# Peripheral.net
KiCad netlist of a schematic drawn in Altium Designer
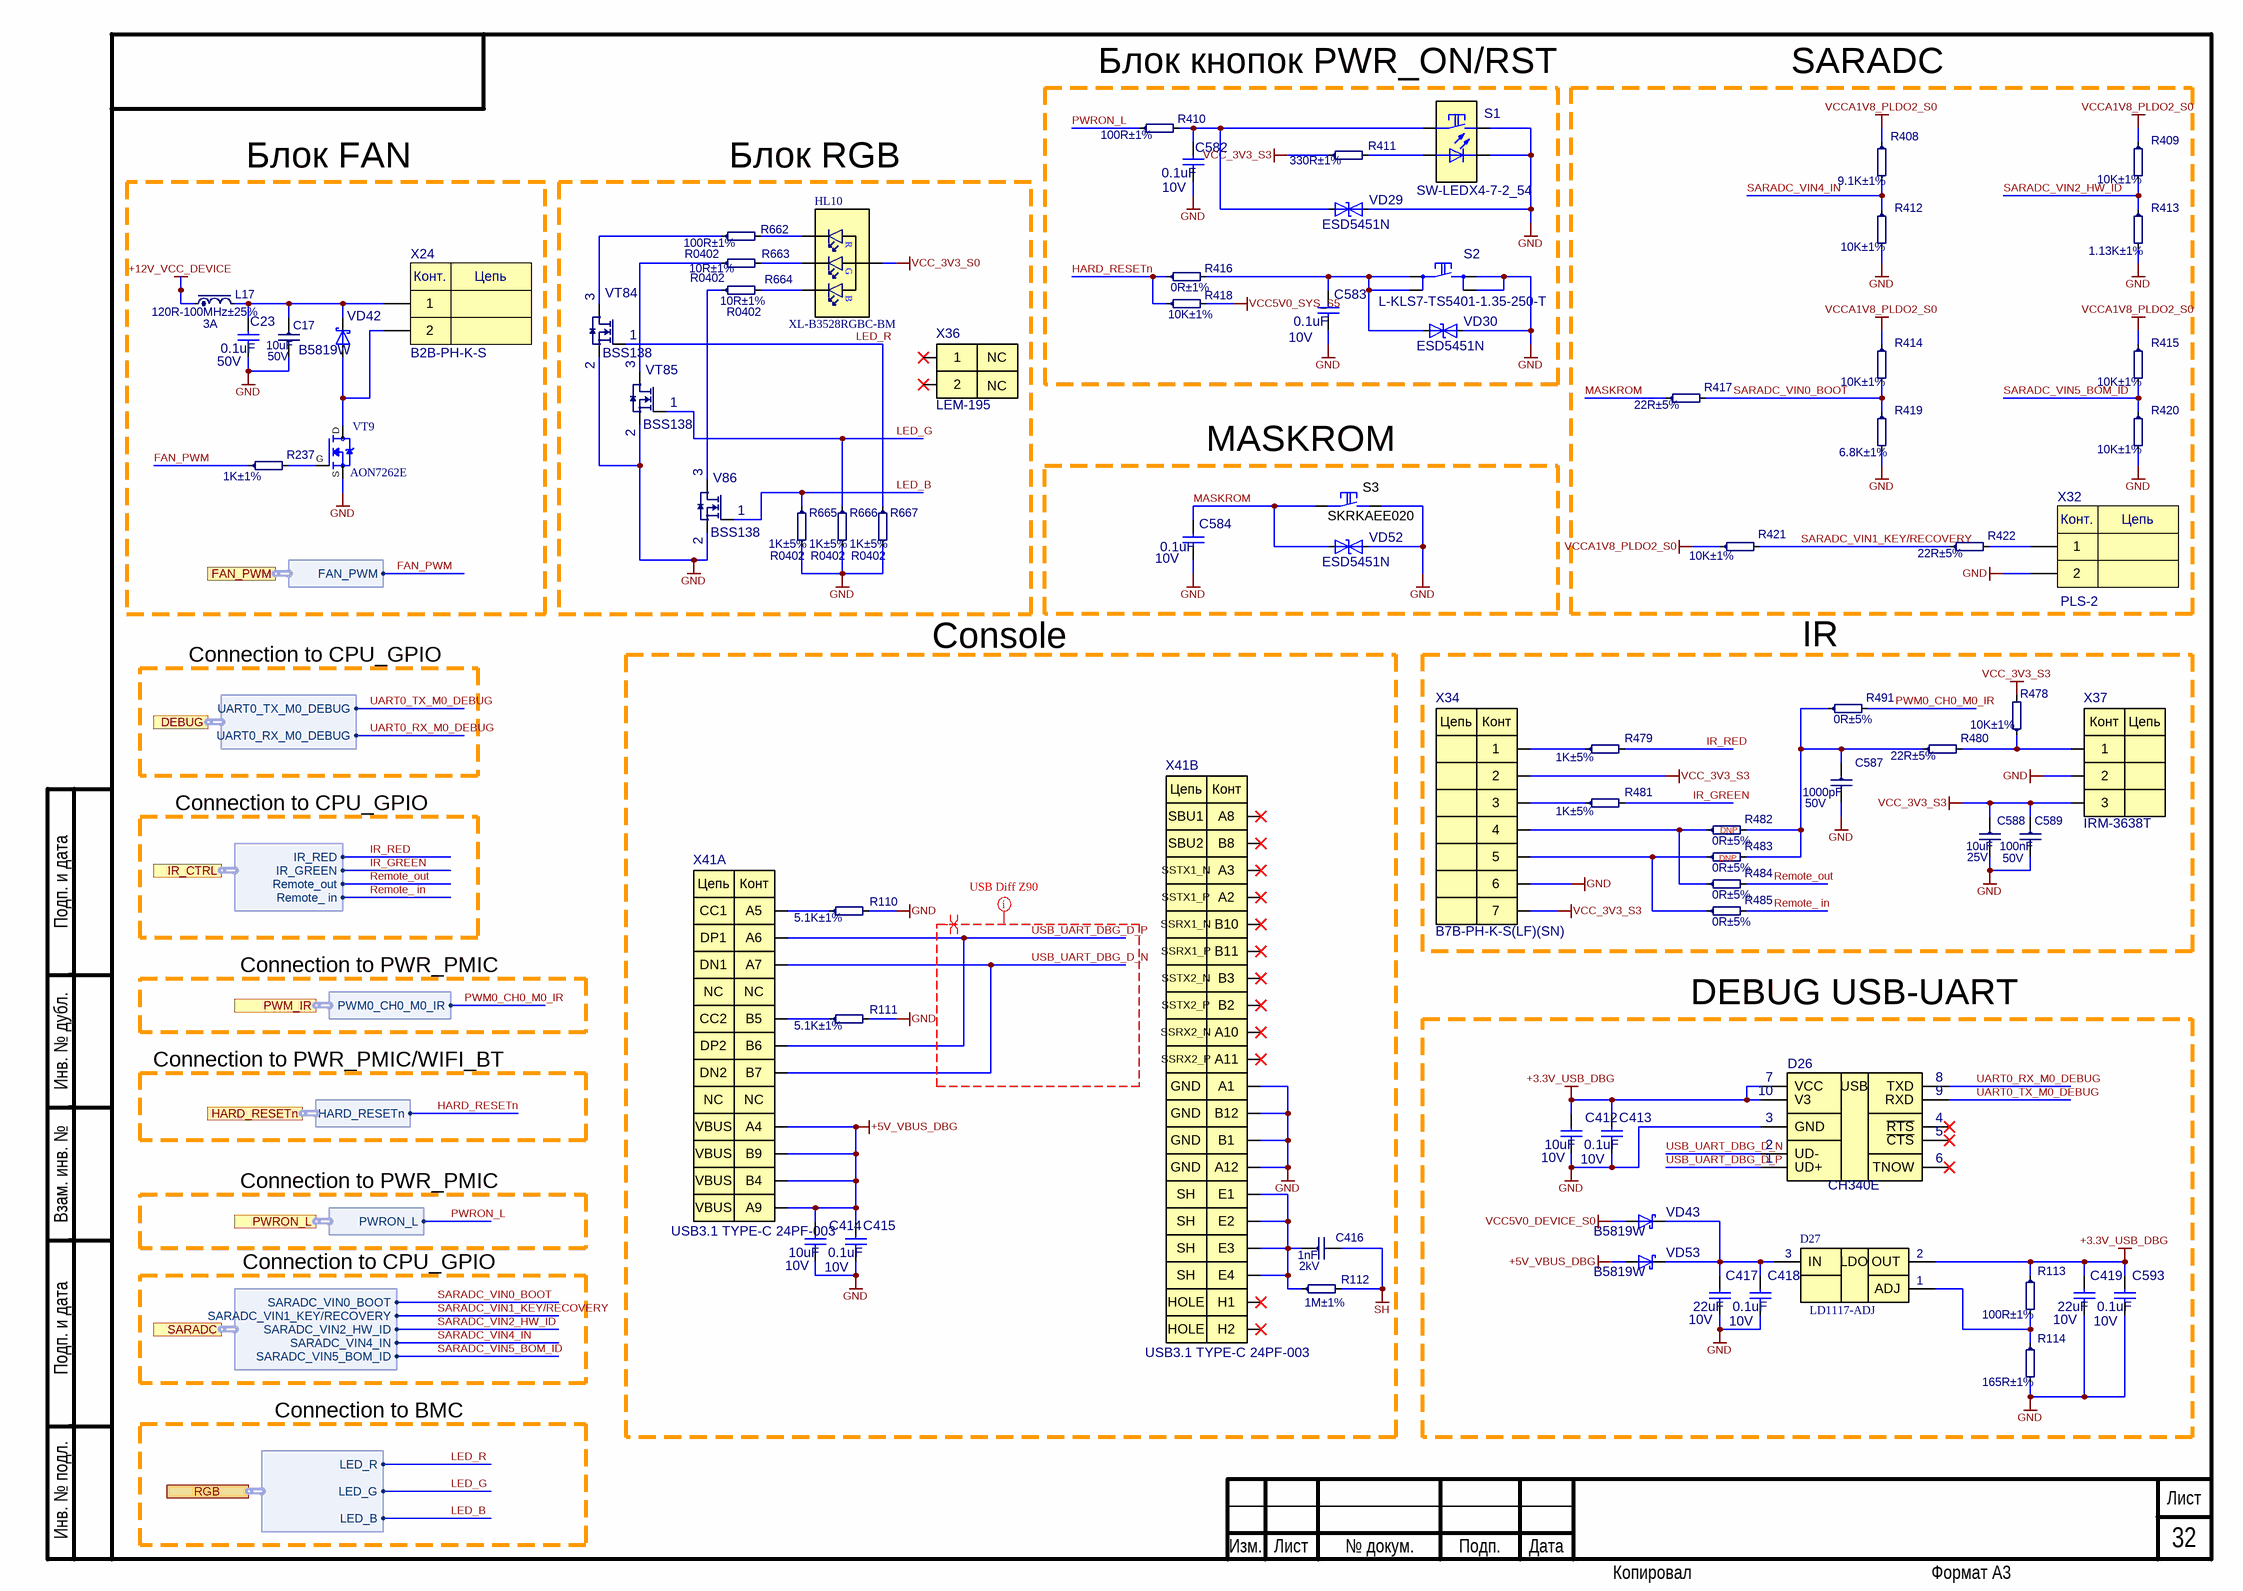
[diagram p0: Peripheral.SchDoc]

(export (version "E")
  (design (tool "Eeschema 10.0.6"))
  (components
    (comp (ref "C17")
      (value "10uF")
      (footprint "C1206")
      (fields
        (field (name "VOLTAGE") "50V")
        (field (name "PART NUMBER") "1206-X5R-50V-010uF±10%")
        (field (name "TOLERANCE") "10%")
        (field (name "MANUFACTURER") "Yageo")
      )
      (libsource (lib "") (part "C_1"))
    )
    (comp (ref "C23")
      (value "0.1uF")
      (footprint "C0402")
      (fields
        (field (name "PART NUMBER") "0402-X5R-50V-0.1uF±10%")
        (field (name "VOLTAGE") "50V")
        (field (name "TOLERANCE") "10%")
        (field (name "MANUFACTURER") "Yageo")
      )
      (libsource (lib "ATB") (part "C"))
    )
    (comp (ref "C412")
      (value "10uF")
      (footprint "C0402")
      (fields
        (field (name "PART NUMBER") "0402-X5R-10V-10uF±20%")
        (field (name "VOLTAGE") "10V")
        (field (name "TOLERANCE") "20%")
        (field (name "MANUFACTURER") "Murata Electronics")
      )
      (libsource (lib "ATB") (part "C"))
    )
    (comp (ref "C413")
      (value "0.1uF")
      (footprint "C0402")
      (fields
        (field (name "PART NUMBER") "0402-X5R-10V-0.1uF±10%")
        (field (name "VOLTAGE") "10V")
        (field (name "TOLERANCE") "10%")
        (field (name "MANUFACTURER") "Yageo")
      )
      (libsource (lib "ATB") (part "C"))
    )
    (comp (ref "C414")
      (value "10uF")
      (footprint "C0402")
      (fields
        (field (name "PART NUMBER") "0402-X5R-10V-10uF±20%")
        (field (name "VOLTAGE") "10V")
        (field (name "TOLERANCE") "20%")
        (field (name "MANUFACTURER") "Murata Electronics")
      )
      (libsource (lib "ATB") (part "C"))
    )
    (comp (ref "C415")
      (value "0.1uF")
      (footprint "C0402")
      (fields
        (field (name "PART NUMBER") "0402-X5R-10V-0.1uF±10%")
        (field (name "VOLTAGE") "10V")
        (field (name "TOLERANCE") "10%")
        (field (name "MANUFACTURER") "Yageo")
      )
      (libsource (lib "ATB") (part "C"))
    )
    (comp (ref "C416")
      (value "1nF")
      (footprint "C1812")
      (fields
        (field (name "VOLTAGE") "2kV")
        (field (name "PART NUMBER") "1812-C0G-2kV-1nF±10%")
        (field (name "TOLERANCE") "5%")
        (field (name "MANUFACTURER") "FH")
      )
      (libsource (lib "") (part "C_1"))
    )
    (comp (ref "C417")
      (value "22uF")
      (footprint "C0603")
      (fields
        (field (name "PART NUMBER") "0603-X5R-10V-22uF±20%")
        (field (name "VOLTAGE") "10V")
        (field (name "TOLERANCE") "20%")
        (field (name "MANUFACTURER") "Murata")
      )
      (libsource (lib "ATB") (part "C"))
    )
    (comp (ref "C418")
      (value "0.1uF")
      (footprint "C0402")
      (fields
        (field (name "PART NUMBER") "0402-X5R-10V-0.1uF±10%")
        (field (name "VOLTAGE") "10V")
        (field (name "TOLERANCE") "10%")
        (field (name "MANUFACTURER") "Yageo")
      )
      (libsource (lib "ATB") (part "C"))
    )
    (comp (ref "C419")
      (value "22uF")
      (footprint "C0603")
      (fields
        (field (name "PART NUMBER") "0603-X5R-10V-22uF±20%")
        (field (name "VOLTAGE") "10V")
        (field (name "TOLERANCE") "20%")
        (field (name "MANUFACTURER") "Murata")
      )
      (libsource (lib "ATB") (part "C"))
    )
    (comp (ref "C582")
      (value "0.1uF")
      (footprint "C0402")
      (fields
        (field (name "PART NUMBER") "0402-X5R-10V-0.1uF±10%")
        (field (name "VOLTAGE") "10V")
        (field (name "TOLERANCE") "10%")
        (field (name "MANUFACTURER") "Yageo")
      )
      (libsource (lib "ATB") (part "C"))
    )
    (comp (ref "C583")
      (value "0.1uF")
      (footprint "C0402")
      (fields
        (field (name "PART NUMBER") "0402-X5R-10V-0.1uF±10%")
        (field (name "VOLTAGE") "10V")
        (field (name "TOLERANCE") "10%")
        (field (name "MANUFACTURER") "Yageo")
      )
      (libsource (lib "ATB") (part "C"))
    )
    (comp (ref "C584")
      (value "0.1uF")
      (footprint "C0402")
      (fields
        (field (name "PART NUMBER") "0402-X5R-10V-0.1uF±10%")
        (field (name "VOLTAGE") "10V")
        (field (name "TOLERANCE") "10%")
        (field (name "MANUFACTURER") "Yageo")
      )
      (libsource (lib "ATB") (part "C"))
    )
    (comp (ref "C587")
      (value "1000pF")
      (footprint "C0402")
      (fields
        (field (name "VOLTAGE") "50V")
        (field (name "PART NUMBER") "0402-NP0-50V-1000pF±5%")
        (field (name "TOLERANCE") "5%")
        (field (name "MANUFACTURER") "Yageo")
      )
      (libsource (lib "") (part "C_1"))
    )
    (comp (ref "C588")
      (value "10uF")
      (footprint "C0805")
      (fields
        (field (name "VOLTAGE") "25V")
        (field (name "PART NUMBER") "0805-X5R-25V-10uF±10%")
        (field (name "TOLERANCE") "10%")
        (field (name "MANUFACTURER") "Samsung")
      )
      (libsource (lib "") (part "C_1"))
    )
    (comp (ref "C589")
      (value "100nF")
      (footprint "C0402")
      (description "Ceramic Capacitor 0402 100nF ±10% 50V X7R")
      (fields
        (field (name "VOLTAGE") "50V")
        (field (name "PART NUMBER") "0402-X7R-50V-0.1uF±10%")
        (field (name "TOLERANCE") "10%")
      )
      (libsource (lib "") (part "C_1"))
    )
    (comp (ref "C593")
      (value "0.1uF")
      (footprint "C0402")
      (fields
        (field (name "PART NUMBER") "0402-X5R-10V-0.1uF±10%")
        (field (name "VOLTAGE") "10V")
        (field (name "TOLERANCE") "10%")
        (field (name "MANUFACTURER") "Yageo")
      )
      (libsource (lib "ATB") (part "C"))
    )
    (comp (ref "D26")
      (value "CH340E")
      (footprint "MSOP-10")
      (description "USB to serial chip")
      (fields (field (name "MANUFACTURER") "WCH"))
      (libsource (lib "ATB") (part "CH340E"))
    )
    (comp (ref "D27")
      (value "LD1117-ADJ")
      (footprint "GM1117S-AST3R")
      (fields (field (name "MANUFACTURER") "UMW"))
      (libsource (lib "LIB_RK") (part "GM1117S-AST3R"))
    )
    (comp (ref "HL10")
      (value "XL-B3528RGBC-BM")
      (footprint "XL-B3528RGBC-BM")
      (description "20mA 无色透明透镜 -40℃~+85℃ Common anode 正贴 RGB 45mW SMD2835-4P Light Emitting Diodes (LED) ROHS")
      (fields (field (name "MANUFACTURER") "XINGLIGHT"))
      (libsource (lib "LIB_RK") (part "XL-B3528RGBC-BM"))
    )
    (comp (ref "L17")
      (value "120R-100MHz±25%")
      (footprint "L0805")
      (fields
        (field (name "CURRENT") "3A")
        (field (name "PART NUMBER") "0805-3A-120R-100MHz")
        (field (name "TOLERANCE") "25%")
        (field (name "MANUFACTURER") "Murata Electronics")
      )
      (libsource (lib "ATB") (part "L"))
    )
    (comp (ref "R110")
      (value "5.1K±1%")
      (footprint "R0402")
      (description "Chip Resistor 0402 5.1kΩ ±1% 50V ±100ppm/℃ Thick Film")
      (fields (field (name "PART NUMBER") "0402-0.0625W-5.1K-100ppm±1%") (field (name "TOLERANCE") "1%"))
      (libsource (lib "ATB") (part "R"))
    )
    (comp (ref "R111")
      (value "5.1K±1%")
      (footprint "R0402")
      (description "Chip Resistor 0402 5.1kΩ ±1% 50V ±100ppm/℃ Thick Film")
      (fields (field (name "PART NUMBER") "0402-0.0625W-5.1K-100ppm±1%") (field (name "TOLERANCE") "1%"))
      (libsource (lib "ATB") (part "R"))
    )
    (comp (ref "R112")
      (value "1M±1%")
      (footprint "R1206")
      (description "Chip Resistor 1206 1MΩ ±1% 200V ±100ppm/℃ Thick Film")
      (fields (field (name "PART NUMBER") "1206-0.25W-1M-100ppm±1%") (field (name "TOLERANCE") "1%"))
      (libsource (lib "ATB") (part "R"))
    )
    (comp (ref "R113")
      (value "100R±1%")
      (footprint "R0402")
      (description "Chip Resistor 0402 100Ω ±1% 50V ±100ppm/℃ Thick Film")
      (fields (field (name "PART NUMBER") "0402-0.0625W-100R-100ppm±1%") (field (name "TOLERANCE") "1%"))
      (libsource (lib "ATB") (part "R"))
    )
    (comp (ref "R114")
      (value "165R±1%")
      (footprint "R0402")
      (description "Chip Resistor 0402 100Ω ±1% 50V ±100ppm/℃ Thick Film")
      (fields (field (name "PART NUMBER") "0402-0.0625W-165R-100ppm±1%") (field (name "TOLERANCE") "1%"))
      (libsource (lib "ATB") (part "R"))
    )
    (comp (ref "R237")
      (value "1K±1%")
      (footprint "R0402")
      (fields
        (field (name "PART NUMBER") "0402-0.0625W-1K-100ppm±1%")
        (field (name "TOLERANCE") "1%")
        (field (name "MANUFACTURER") "Yageo")
      )
      (libsource (lib "ATB") (part "R"))
    )
    (comp (ref "R408")
      (value "9.1K±1%")
      (footprint "R0402")
      (fields
        (field (name "PART NUMBER") "0402-0.0625W-9.1K-100ppm±1%")
        (field (name "TOLERANCE") "1%")
        (field (name "MANUFACTURER") "Yageo")
      )
      (libsource (lib "ATB") (part "R"))
    )
    (comp (ref "R409")
      (value "10K±1%")
      (footprint "R0402")
      (description "Chip Resistor 0402 10kΩ ±1% 50V ±100ppm/℃ Thick Film")
      (fields (field (name "PART NUMBER") "0402-0.0625W-10K-100ppm±1%") (field (name "TOLERANCE") "1%"))
      (libsource (lib "ATB") (part "R"))
    )
    (comp (ref "R410")
      (value "100R±1%")
      (footprint "R0402")
      (description "Chip Resistor 0402 100Ω ±1% 50V ±100ppm/℃ Thick Film")
      (fields (field (name "PART NUMBER") "0402-0.0625W-100R-100ppm±1%") (field (name "TOLERANCE") "1%"))
      (libsource (lib "ATB") (part "R"))
    )
    (comp (ref "R411")
      (value "330R±1%")
      (footprint "R0402")
      (fields
        (field (name "PART NUMBER") "0402-0.0625W-330R-100ppm±1%")
        (field (name "TOLERANCE") "1%")
        (field (name "MANUFACTURER") "Yageo")
      )
      (libsource (lib "ATB") (part "R"))
    )
    (comp (ref "R412")
      (value "10K±1%")
      (footprint "R0402")
      (description "Chip Resistor 0402 10kΩ ±1% 50V ±100ppm/℃ Thick Film")
      (fields (field (name "PART NUMBER") "0402-0.0625W-10K-100ppm±1%") (field (name "TOLERANCE") "1%"))
      (libsource (lib "ATB") (part "R"))
    )
    (comp (ref "R413")
      (value "1.13K±1%")
      (footprint "R0402")
      (description "Chip Resistor 0402 10kΩ ±1% 50V ±100ppm/℃ Thick Film")
      (fields (field (name "PART NUMBER") "0402-0.0625W-1.13K-100ppm±1%") (field (name "TOLERANCE") "1%"))
      (libsource (lib "ATB") (part "R"))
    )
    (comp (ref "R414")
      (value "10K±1%")
      (footprint "R0402")
      (description "Chip Resistor 0402 10kΩ ±1% 50V ±100ppm/℃ Thick Film")
      (fields (field (name "PART NUMBER") "0402-0.0625W-10K-100ppm±1%") (field (name "TOLERANCE") "1%"))
      (libsource (lib "ATB") (part "R"))
    )
    (comp (ref "R415")
      (value "10K±1%")
      (footprint "R0402")
      (description "Chip Resistor 0402 10kΩ ±1% 50V ±100ppm/℃ Thick Film")
      (fields (field (name "PART NUMBER") "0402-0.0625W-10K-100ppm±1%") (field (name "TOLERANCE") "1%"))
      (libsource (lib "ATB") (part "R"))
    )
    (comp (ref "R416")
      (value "0R±1%")
      (footprint "R0402")
      (description "Chip Resistor 0402 0Ω ±1% 50V ±100ppm/℃ Thick Film")
      (fields (field (name "PART NUMBER") "0402-0.0625W-0R-100ppm±1%") (field (name "TOLERANCE") "1%"))
      (libsource (lib "ATB") (part "R"))
    )
    (comp (ref "R417")
      (value "22R±5%")
      (footprint "R0402")
      (fields
        (field (name "PART NUMBER") "0402-0.0625W-22R-100ppm±5%")
        (field (name "TOLERANCE") "5%")
        (field (name "MANUFACTURER") "Yageo")
      )
      (libsource (lib "ATB") (part "R"))
    )
    (comp (ref "R418")
      (value "10K±1%")
      (footprint "R0402")
      (description "Chip Resistor 0402 10kΩ ±1% 50V ±100ppm/℃ Thick Film")
      (fields (field (name "PART NUMBER") "0402-0.0625W-10K-100ppm±1%") (field (name "TOLERANCE") "1%"))
      (libsource (lib "ATB") (part "R"))
    )
    (comp (ref "R419")
      (value "6.8K±1%")
      (footprint "R0402")
      (fields
        (field (name "PART NUMBER") "0402-0.0625W-6.8K-100ppm±1%")
        (field (name "TOLERANCE") "1%")
        (field (name "MANUFACTURER") "Yageo")
      )
      (libsource (lib "ATB") (part "R"))
    )
    (comp (ref "R420")
      (value "10K±1%")
      (footprint "R0402")
      (description "Chip Resistor 0402 10kΩ ±1% 50V ±100ppm/℃ Thick Film")
      (fields (field (name "PART NUMBER") "0402-0.0625W-10K-100ppm±1%") (field (name "TOLERANCE") "1%"))
      (libsource (lib "ATB") (part "R"))
    )
    (comp (ref "R421")
      (value "10K±1%")
      (footprint "R0402")
      (description "Chip Resistor 0402 10kΩ ±1% 50V ±100ppm/℃ Thick Film")
      (fields (field (name "PART NUMBER") "0402-0.0625W-10K-100ppm±1%") (field (name "TOLERANCE") "1%"))
      (libsource (lib "ATB") (part "R"))
    )
    (comp (ref "R422")
      (value "22R±5%")
      (footprint "R0402")
      (fields
        (field (name "PART NUMBER") "0402-0.0625W-22R-100ppm±5%")
        (field (name "TOLERANCE") "5%")
        (field (name "MANUFACTURER") "Yageo")
      )
      (libsource (lib "ATB") (part "R"))
    )
    (comp (ref "R478")
      (value "10K±1%")
      (footprint "R0402")
      (description "Chip Resistor 0402 10kΩ ±1% 50V ±100ppm/℃ Thick Film")
      (fields (field (name "PART NUMBER") "0402-0.0625W-10K-100ppm±1%") (field (name "TOLERANCE") "1%"))
      (libsource (lib "ATB") (part "R"))
    )
    (comp (ref "R479")
      (value "1K±5%")
      (footprint "R0402")
      (fields
        (field (name "PART NUMBER") "0402-0.0625W-1K-100ppm±5%")
        (field (name "TOLERANCE") "5%")
        (field (name "MANUFACTURER") "Yageo")
      )
      (libsource (lib "ATB") (part "R"))
    )
    (comp (ref "R480")
      (value "22R±5%")
      (footprint "R0402")
      (fields
        (field (name "PART NUMBER") "0402-0.0625W-22R-100ppm±5%")
        (field (name "TOLERANCE") "5%")
        (field (name "MANUFACTURER") "Yageo")
      )
      (libsource (lib "ATB") (part "R"))
    )
    (comp (ref "R481")
      (value "1K±5%")
      (footprint "R0402")
      (fields
        (field (name "PART NUMBER") "0402-0.0625W-1K-100ppm±5%")
        (field (name "TOLERANCE") "5%")
        (field (name "MANUFACTURER") "Yageo")
      )
      (libsource (lib "ATB") (part "R"))
    )
    (comp (ref "R482")
      (value "0R±5%")
      (footprint "R0402")
      (fields
        (field (name "PART NUMBER") "0402-0.0625W-0R-100ppm±5%")
        (field (name "TOLERANCE") "5%")
        (field (name "MANUFACTURER") "Yageo")
      )
      (libsource (lib "ATB") (part "R"))
    )
    (comp (ref "R483")
      (value "0R±5%")
      (footprint "R0402")
      (fields
        (field (name "PART NUMBER") "0402-0.0625W-0R-100ppm±5%")
        (field (name "TOLERANCE") "5%")
        (field (name "MANUFACTURER") "Yageo")
      )
      (libsource (lib "ATB") (part "R"))
    )
    (comp (ref "R484")
      (value "0R±5%")
      (footprint "R0402")
      (fields
        (field (name "PART NUMBER") "0402-0.0625W-0R-100ppm±5%")
        (field (name "TOLERANCE") "5%")
        (field (name "MANUFACTURER") "Yageo")
      )
      (libsource (lib "ATB") (part "R"))
    )
    (comp (ref "R485")
      (value "0R±5%")
      (footprint "R0402")
      (fields
        (field (name "PART NUMBER") "0402-0.0625W-0R-100ppm±5%")
        (field (name "TOLERANCE") "5%")
        (field (name "MANUFACTURER") "Yageo")
      )
      (libsource (lib "ATB") (part "R"))
    )
    (comp (ref "R491")
      (value "0R±5%")
      (footprint "R0402")
      (fields
        (field (name "PART NUMBER") "0402-0.0625W-0R-100ppm±5%")
        (field (name "TOLERANCE") "5%")
        (field (name "MANUFACTURER") "Yageo")
      )
      (libsource (lib "ATB") (part "R"))
    )
    (comp (ref "R662")
      (value "100R±1%")
      (footprint "R0402")
      (description "Chip Resistor 0402 100Ω ±1% 50V ±100ppm/℃ Thick Film")
      (fields
        (field (name "CASE") "R0402")
        (field (name "PART NUMBER") "0402-0.0625W-100R-100ppm±1%")
        (field (name "TOLERANCE") "1%")
      )
      (libsource (lib "ATB") (part "R"))
    )
    (comp (ref "R663")
      (value "10R±1%")
      (footprint "R0402")
      (fields
        (field (name "CASE") "R0402")
        (field (name "PART NUMBER") "0402-0.0625W-10R-200ppm±1%")
        (field (name "TOLERANCE") "1%")
        (field (name "MANUFACTURER") "Yageo")
      )
      (libsource (lib "ATB") (part "R"))
    )
    (comp (ref "R664")
      (value "10R±1%")
      (footprint "R0402")
      (fields
        (field (name "CASE") "R0402")
        (field (name "PART NUMBER") "0402-0.0625W-10R-200ppm±1%")
        (field (name "TOLERANCE") "1%")
        (field (name "MANUFACTURER") "Yageo")
      )
      (libsource (lib "ATB") (part "R"))
    )
    (comp (ref "R665")
      (value "1K±5%")
      (footprint "R0402")
      (fields
        (field (name "CASE") "R0402")
        (field (name "PART NUMBER") "0402-0.0625W-1K-100ppm±5%")
        (field (name "TOLERANCE") "5%")
        (field (name "MANUFACTURER") "Yageo")
      )
      (libsource (lib "ATB") (part "R"))
    )
    (comp (ref "R666")
      (value "1K±5%")
      (footprint "R0402")
      (fields
        (field (name "CASE") "R0402")
        (field (name "PART NUMBER") "0402-0.0625W-1K-100ppm±5%")
        (field (name "TOLERANCE") "5%")
        (field (name "MANUFACTURER") "Yageo")
      )
      (libsource (lib "ATB") (part "R"))
    )
    (comp (ref "R667")
      (value "1K±5%")
      (footprint "R0402")
      (fields
        (field (name "CASE") "R0402")
        (field (name "PART NUMBER") "0402-0.0625W-1K-100ppm±5%")
        (field (name "TOLERANCE") "5%")
        (field (name "MANUFACTURER") "Yageo")
      )
      (libsource (lib "ATB") (part "R"))
    )
    (comp (ref "S1")
      (value "SW-LEDX4-7-2_54")
      (footprint "SW-LEDX4-7-2_54")
      (fields (field (name "MANUFACTURER") "FVWIN Electronics"))
      (libsource (lib "LIB_RK") (part "SW-LEDX4-7-2_54"))
    )
    (comp (ref "S2")
      (value "L-KLS7-TS5401-1.35-250-T")
      (footprint "KLS7-TS5401")
      (description "Switch")
      (fields (field (name "MANUFACTURER") "KLS Electronic"))
      (libsource (lib "ATB") (part "Knopka"))
    )
    (comp (ref "S3")
      (value "SKRKAEE020")
      (footprint "SKRKAEE020")
      (description "12V 2.9mm Round Button 3.9mm SPST 50mA SMD,3.9x2.9mm Tactile Switches RoHS")
      (fields (field (name "MANUFACTURER") "ALPSALPINE"))
      (libsource (lib "LIB_RK") (part "SKRKAEE020"))
    )
    (comp (ref "V86")
      (value "BSS138")
      (footprint "SOT23")
      (description "N-Channel Enhancement Mode Field Effect Transistor")
      (fields (field (name "VOLTAGE") "50V") (field (name "MANUFACTURER") "Yangjie"))
      (libsource (lib "ATB") (part "BSS138"))
    )
    (comp (ref "VD29")
      (value "ESD5451N")
      (footprint "DFN_1006_2")
      (description "Diode")
      (fields (field (name "MANUFACTURER") "Tech Public Co."))
      (libsource (lib "ATB") (part "Bi-der_diode"))
    )
    (comp (ref "VD30")
      (value "ESD5451N")
      (footprint "DFN_1006_2")
      (description "Diode")
      (fields (field (name "MANUFACTURER") "Tech Public Co."))
      (libsource (lib "ATB") (part "Bi-der_diode"))
    )
    (comp (ref "VD42")
      (value "B5819W")
      (footprint "B5819W")
      (fields (field (name "MANUFACTURER") "MDD"))
      (libsource (lib "LIB_RK") (part "B5819W"))
    )
    (comp (ref "VD43")
      (value "B5819W")
      (footprint "B5819W")
      (fields (field (name "MANUFACTURER") "MDD"))
      (libsource (lib "LIB_RK") (part "B5819W"))
    )
    (comp (ref "VD52")
      (value "ESD5451N")
      (footprint "DFN_1006_2")
      (description "Diode")
      (fields (field (name "MANUFACTURER") "Tech Public Co."))
      (libsource (lib "ATB") (part "Bi-der_diode"))
    )
    (comp (ref "VD53")
      (value "B5819W")
      (footprint "B5819W")
      (fields (field (name "MANUFACTURER") "MDD"))
      (libsource (lib "LIB_RK") (part "B5819W"))
    )
    (comp (ref "VT9")
      (value "AON7262E")
      (footprint "AON7262E")
      (description "60V 6.2mΩ@10V,20A 2.2V@250uA N Channel DFN-8(3.3x3.3) MOSFET")
      (fields (field (name "MANUFACTURER") "Alpha & Omega"))
      (libsource (lib "LIB_RK") (part "AON7262E"))
    )
    (comp (ref "VT84")
      (value "BSS138")
      (footprint "SOT23")
      (description "N-Channel Enhancement Mode Field Effect Transistor")
      (fields (field (name "VOLTAGE") "50V") (field (name "MANUFACTURER") "Yangjie"))
      (libsource (lib "ATB") (part "BSS138"))
    )
    (comp (ref "VT85")
      (value "BSS138")
      (footprint "SOT23")
      (description "N-Channel Enhancement Mode Field Effect Transistor")
      (fields (field (name "VOLTAGE") "50V") (field (name "MANUFACTURER") "Yangjie"))
      (libsource (lib "ATB") (part "BSS138"))
    )
    (comp (ref "X24")
      (value "B2B-PH-K-S")
      (footprint "B2B-PH-K-S")
      (description "1x2P PH 2mm Connector")
      (fields (field (name "MANUFACTURER") "JST Sales America Inc."))
      (libsource (lib "ATB") (part "H2"))
    )
    (comp (ref "X32")
      (value "PLS-2")
      (footprint "PLS2")
      (description "Terminal block 2")
      (libsource (lib "ATB") (part "H2"))
    )
    (comp (ref "X34")
      (value "B7B-PH-K-S(LF)(SN)")
      (footprint "B7B-PH-K-S(LF)(SN)")
      (description "Connector Header 7 position 2mm Pitch 2A Through Hole -25℃~+85℃")
      (fields (field (name "MANUFACTURER") "JST"))
      (libsource (lib "LIB_RK") (part "B7B-PH-K-S(LF)(SN)"))
    )
    (comp (ref "X36")
      (value "LEM-195")
      (footprint "LEM-195")
      (fields (field (name "MANUFACTURER") "Kang Yang"))
      (libsource (lib "LIB_RK") (part "LEM-195"))
    )
    (comp (ref "X37")
      (value "IRM-3638T")
      (footprint "IRM-3638T")
      (description "SIP-3-2.54mm Photo Detectors - Remote Receiver RoHS")
      (fields (field (name "MANUFACTURER") "EVERLIGHT"))
      (libsource (lib "LIB_RK") (part "IRM-3638T"))
    )
    (comp (ref "X41")
      (value "USB3.1 TYPE-C 24PF-003")
      (footprint "USB3.1 TYPE-C 24PF-003")
      (description "Разъем USB USB3.1 TYPE-C 24PF-003, 24 контакта")
      (fields (field (name "MANUFACTURER") "RUICHI"))
      (libsource (lib "") (part "USB3.1 TYPE-C 24PF-003_1"))
    )
  )
  (nets
    (net (code "6") (name "+3.3V_USB_DBG") (class "Default")
      (node (ref "C412") (pin "2") (pinfunction "2_2") (pintype "passive"))
      (node (ref "C413") (pin "2") (pinfunction "2_2") (pintype "passive"))
      (node (ref "C419") (pin "2") (pinfunction "2_2") (pintype "passive"))
      (node (ref "C593") (pin "2") (pinfunction "2_2") (pintype "passive"))
      (node (ref "D26") (pin "10") (pinfunction "V3_10") (pintype "passive"))
      (node (ref "D26") (pin "7") (pinfunction "VCC_7") (pintype "passive"))
      (node (ref "D27") (pin "2") (pinfunction "OUT_2") (pintype "passive"))
      (node (ref "R113") (pin "1") (pinfunction "1_1") (pintype "passive"))
    )
    (net (code "7") (name "+5V_VBUS_DBG") (class "Default")
      (node (ref "C414") (pin "2") (pinfunction "2_2") (pintype "passive"))
      (node (ref "C415") (pin "2") (pinfunction "2_2") (pintype "passive"))
      (node (ref "VD53") (pin "2") (pinfunction "A_2") (pintype "passive"))
      (node (ref "X41") (pin "A4") (pinfunction "VBUS_A4") (pintype "passive"))
      (node (ref "X41") (pin "A9") (pinfunction "VBUS_A9") (pintype "passive"))
      (node (ref "X41") (pin "B4") (pinfunction "VBUS_B4") (pintype "passive"))
      (node (ref "X41") (pin "B9") (pinfunction "VBUS_B9") (pintype "passive"))
    )
    (net (code "8") (name "+12V_VCC_DEVICE") (class "Default")
      (node (ref "L17") (pin "1") (pinfunction "1_1") (pintype "passive"))
    )
    (net (code "9") (name "/FAN_PWM") (class "Default")
      (node (ref "R237") (pin "1") (pinfunction "1_1") (pintype "passive"))
    )
    (net (code "10") (name "/HARD_RESETn") (class "Default")
      (node (ref "R416") (pin "1") (pinfunction "1_1") (pintype "passive"))
      (node (ref "R418") (pin "1") (pinfunction "1_1") (pintype "passive"))
    )
    (net (code "11") (name "/IR_GREEN") (class "Default")
      (node (ref "R481") (pin "2") (pinfunction "2_2") (pintype "passive"))
    )
    (net (code "12") (name "/IR_RED") (class "Default")
      (node (ref "R479") (pin "2") (pinfunction "2_2") (pintype "passive"))
    )
    (net (code "13") (name "/LED_B") (class "Default")
      (node (ref "R665") (pin "1") (pinfunction "1_1") (pintype "passive"))
      (node (ref "V86") (pin "1") (pinfunction "G_1") (pintype "passive"))
    )
    (net (code "14") (name "/LED_G") (class "Default")
      (node (ref "R666") (pin "1") (pinfunction "1_1") (pintype "passive"))
      (node (ref "VT85") (pin "1") (pinfunction "G_1") (pintype "passive"))
    )
    (net (code "15") (name "/LED_R") (class "Default")
      (node (ref "R667") (pin "1") (pinfunction "1_1") (pintype "passive"))
      (node (ref "VT84") (pin "1") (pinfunction "G_1") (pintype "passive"))
    )
    (net (code "16") (name "/MASKROM") (class "Default")
      (node (ref "C584") (pin "2") (pinfunction "2_2") (pintype "passive"))
      (node (ref "R417") (pin "1") (pinfunction "1_1") (pintype "passive"))
      (node (ref "S3") (pin "1") (pinfunction "1_1") (pintype "passive"))
      (node (ref "VD52") (pin "2") (pinfunction "2_2") (pintype "passive"))
    )
    (net (code "17") (name "/PWM0_CH0_M0_IR") (class "Default")
      (node (ref "R491") (pin "2") (pinfunction "2_2") (pintype "passive"))
    )
    (net (code "18") (name "/PWRON_L") (class "Default")
      (node (ref "R410") (pin "1") (pinfunction "1_1") (pintype "passive"))
    )
    (net (code "19") (name "/Remote_ in") (class "Default")
      (node (ref "R485") (pin "2") (pinfunction "2_2") (pintype "passive"))
    )
    (net (code "20") (name "/Remote_out") (class "Default")
      (node (ref "R484") (pin "2") (pinfunction "2_2") (pintype "passive"))
    )
    (net (code "21") (name "/SARADC_VIN0_BOOT") (class "Default")
      (node (ref "R414") (pin "2") (pinfunction "2_2") (pintype "passive"))
      (node (ref "R417") (pin "2") (pinfunction "2_2") (pintype "passive"))
      (node (ref "R419") (pin "1") (pinfunction "1_1") (pintype "passive"))
    )
    (net (code "22") (name "/SARADC_VIN1_KEY{slash}RECOVERY") (class "Default")
      (node (ref "R421") (pin "2") (pinfunction "2_2") (pintype "passive"))
      (node (ref "R422") (pin "1") (pinfunction "1_1") (pintype "passive"))
    )
    (net (code "23") (name "/SARADC_VIN2_HW_ID") (class "Default")
      (node (ref "R409") (pin "2") (pinfunction "2_2") (pintype "passive"))
      (node (ref "R413") (pin "1") (pinfunction "1_1") (pintype "passive"))
    )
    (net (code "24") (name "/SARADC_VIN4_IN") (class "Default")
      (node (ref "R408") (pin "2") (pinfunction "2_2") (pintype "passive"))
      (node (ref "R412") (pin "1") (pinfunction "1_1") (pintype "passive"))
    )
    (net (code "25") (name "/SARADC_VIN5_BOM_ID") (class "Default")
      (node (ref "R415") (pin "2") (pinfunction "2_2") (pintype "passive"))
      (node (ref "R420") (pin "1") (pinfunction "1_1") (pintype "passive"))
    )
    (net (code "26") (name "/UART0_RX_M0_DEBUG") (class "Default")
      (node (ref "D26") (pin "8") (pinfunction "TXD_8") (pintype "passive"))
    )
    (net (code "27") (name "/UART0_TX_M0_DEBUG") (class "Default")
      (node (ref "D26") (pin "9") (pinfunction "RXD_9") (pintype "passive"))
    )
    (net (code "28") (name "/USB_UART_DBG_D_N") (class "Default")
      (node (ref "D26") (pin "2") (pinfunction "UD-_2") (pintype "passive"))
      (node (ref "X41") (pin "A7") (pinfunction "DN1_A7") (pintype "passive"))
      (node (ref "X41") (pin "B7") (pinfunction "DN2_B7") (pintype "passive"))
    )
    (net (code "29") (name "/USB_UART_DBG_D_P") (class "Default")
      (node (ref "D26") (pin "1") (pinfunction "UD+_1") (pintype "passive"))
      (node (ref "X41") (pin "A6") (pinfunction "DP1_A6") (pintype "passive"))
      (node (ref "X41") (pin "B6") (pinfunction "DP2_B6") (pintype "passive"))
    )
    (net (code "38") (name "GND") (class "Default")
      (node (ref "C17") (pin "2") (pinfunction "2_2") (pintype "passive"))
      (node (ref "C23") (pin "1") (pinfunction "1_1") (pintype "passive"))
      (node (ref "C412") (pin "1") (pinfunction "1_1") (pintype "passive"))
      (node (ref "C413") (pin "1") (pinfunction "1_1") (pintype "passive"))
      (node (ref "C414") (pin "1") (pinfunction "1_1") (pintype "passive"))
      (node (ref "C415") (pin "1") (pinfunction "1_1") (pintype "passive"))
      (node (ref "C417") (pin "1") (pinfunction "1_1") (pintype "passive"))
      (node (ref "C418") (pin "1") (pinfunction "1_1") (pintype "passive"))
      (node (ref "C419") (pin "1") (pinfunction "1_1") (pintype "passive"))
      (node (ref "C582") (pin "1") (pinfunction "1_1") (pintype "passive"))
      (node (ref "C583") (pin "1") (pinfunction "1_1") (pintype "passive"))
      (node (ref "C584") (pin "1") (pinfunction "1_1") (pintype "passive"))
      (node (ref "C587") (pin "2") (pinfunction "2_2") (pintype "passive"))
      (node (ref "C588") (pin "2") (pinfunction "2_2") (pintype "passive"))
      (node (ref "C589") (pin "2") (pinfunction "2_2") (pintype "passive"))
      (node (ref "C593") (pin "1") (pinfunction "1_1") (pintype "passive"))
      (node (ref "D26") (pin "3") (pinfunction "GND_3") (pintype "passive"))
      (node (ref "R110") (pin "2") (pinfunction "2_2") (pintype "passive"))
      (node (ref "R111") (pin "2") (pinfunction "2_2") (pintype "passive"))
      (node (ref "R114") (pin "2") (pinfunction "2_2") (pintype "passive"))
      (node (ref "R412") (pin "2") (pinfunction "2_2") (pintype "passive"))
      (node (ref "R413") (pin "2") (pinfunction "2_2") (pintype "passive"))
      (node (ref "R419") (pin "2") (pinfunction "2_2") (pintype "passive"))
      (node (ref "R420") (pin "2") (pinfunction "2_2") (pintype "passive"))
      (node (ref "R665") (pin "2") (pinfunction "2_2") (pintype "passive"))
      (node (ref "R666") (pin "2") (pinfunction "2_2") (pintype "passive"))
      (node (ref "R667") (pin "2") (pinfunction "2_2") (pintype "passive"))
      (node (ref "S1") (pin "2") (pinfunction "2_2") (pintype "passive"))
      (node (ref "S1") (pin "L2") (pinfunction "C_L2") (pintype "passive"))
      (node (ref "S2") (pin "3") (pinfunction "3_3") (pintype "passive"))
      (node (ref "S2") (pin "4") (pinfunction "4_4") (pintype "passive"))
      (node (ref "S3") (pin "2") (pinfunction "2_2") (pintype "passive"))
      (node (ref "V86") (pin "2") (pinfunction "S_2") (pintype "passive"))
      (node (ref "VD29") (pin "1") (pinfunction "1_1") (pintype "passive"))
      (node (ref "VD30") (pin "1") (pinfunction "1_1") (pintype "passive"))
      (node (ref "VD52") (pin "1") (pinfunction "1_1") (pintype "passive"))
      (node (ref "VT84") (pin "2") (pinfunction "S_2") (pintype "passive"))
      (node (ref "VT85") (pin "2") (pinfunction "S_2") (pintype "passive"))
      (node (ref "VT9") (pin "S") (pinfunction "S_S") (pintype "passive"))
      (node (ref "X32") (pin "2") (pinfunction "2_2") (pintype "passive"))
      (node (ref "X34") (pin "6") (pinfunction "6_6") (pintype "passive"))
      (node (ref "X37") (pin "2") (pinfunction "2_2") (pintype "passive"))
      (node (ref "X41") (pin "A12") (pinfunction "GND_A12") (pintype "passive"))
      (node (ref "X41") (pin "B1") (pinfunction "GND_B1") (pintype "passive"))
      (node (ref "X41") (pin "B12") (pinfunction "GND_B12") (pintype "passive"))
    )
    (net (code "39") (name "Net-(C416-Pad1)") (class "Default")
      (node (ref "C416") (pin "1") (pinfunction "1_1") (pintype "passive"))
      (node (ref "R112") (pin "1") (pinfunction "1_1") (pintype "passive"))
      (node (ref "X41") (pin "E1") (pinfunction "SH_E1") (pintype "passive"))
      (node (ref "X41") (pin "E2") (pinfunction "SH_E2") (pintype "passive"))
      (node (ref "X41") (pin "E3") (pinfunction "SH_E3") (pintype "passive"))
      (node (ref "X41") (pin "E4") (pinfunction "SH_E4") (pintype "passive"))
    )
    (net (code "40") (name "Net-(C582-Pad2)") (class "Default")
      (node (ref "C582") (pin "2") (pinfunction "2_2") (pintype "passive"))
      (node (ref "R410") (pin "2") (pinfunction "2_2") (pintype "passive"))
      (node (ref "S1") (pin "1") (pinfunction "1_1") (pintype "passive"))
      (node (ref "VD29") (pin "2") (pinfunction "2_2") (pintype "passive"))
    )
    (net (code "41") (name "Net-(C583-Pad2)") (class "Default")
      (node (ref "C583") (pin "2") (pinfunction "2_2") (pintype "passive"))
      (node (ref "R416") (pin "2") (pinfunction "2_2") (pintype "passive"))
      (node (ref "S2") (pin "1") (pinfunction "1_1") (pintype "passive"))
      (node (ref "S2") (pin "2") (pinfunction "2_2") (pintype "passive"))
      (node (ref "VD30") (pin "2") (pinfunction "2_2") (pintype "passive"))
    )
    (net (code "42") (name "Net-(C587-Pad1)") (class "Default")
      (node (ref "C587") (pin "1") (pinfunction "1_1") (pintype "passive"))
      (node (ref "R480") (pin "1") (pinfunction "1_1") (pintype "passive"))
      (node (ref "R482") (pin "2") (pinfunction "2_2") (pintype "passive"))
      (node (ref "R483") (pin "2") (pinfunction "2_2") (pintype "passive"))
      (node (ref "R491") (pin "1") (pinfunction "1_1") (pintype "passive"))
    )
    (net (code "43") (name "Net-(D27-ADJ)") (class "Default")
      (node (ref "D27") (pin "1") (pinfunction "ADJ_1") (pintype "passive"))
      (node (ref "R113") (pin "2") (pinfunction "2_2") (pintype "passive"))
      (node (ref "R114") (pin "1") (pinfunction "1_1") (pintype "passive"))
    )
    (net (code "44") (name "Net-(D27-IN)") (class "Default")
      (node (ref "C417") (pin "2") (pinfunction "2_2") (pintype "passive"))
      (node (ref "C418") (pin "2") (pinfunction "2_2") (pintype "passive"))
      (node (ref "D27") (pin "3") (pinfunction "IN_3") (pintype "passive"))
      (node (ref "VD43") (pin "1") (pinfunction "K_1") (pintype "passive"))
      (node (ref "VD53") (pin "1") (pinfunction "K_1") (pintype "passive"))
    )
    (net (code "45") (name "Net-(HL10-Pad1)") (class "Default")
      (node (ref "HL10") (pin "1") (pinfunction "1_1") (pintype "passive"))
      (node (ref "R662") (pin "2") (pinfunction "2_2") (pintype "passive"))
    )
    (net (code "46") (name "Net-(HL10-Pad3)") (class "Default")
      (node (ref "HL10") (pin "3") (pinfunction "3_3") (pintype "passive"))
      (node (ref "R663") (pin "2") (pinfunction "2_2") (pintype "passive"))
    )
    (net (code "47") (name "Net-(HL10-Pad4)") (class "Default")
      (node (ref "HL10") (pin "4") (pinfunction "4_4") (pintype "passive"))
      (node (ref "R664") (pin "2") (pinfunction "2_2") (pintype "passive"))
    )
    (net (code "48") (name "Net-(R237-Pad2)") (class "Default")
      (node (ref "R237") (pin "2") (pinfunction "2_2") (pintype "passive"))
      (node (ref "VT9") (pin "G") (pinfunction "G_G") (pintype "passive"))
    )
    (net (code "49") (name "Net-(R422-Pad2)") (class "Default")
      (node (ref "R422") (pin "2") (pinfunction "2_2") (pintype "passive"))
      (node (ref "X32") (pin "1") (pinfunction "1_1") (pintype "passive"))
    )
    (net (code "50") (name "Net-(R478-Pad1)") (class "Default")
      (node (ref "R478") (pin "1") (pinfunction "1_1") (pintype "passive"))
      (node (ref "R480") (pin "2") (pinfunction "2_2") (pintype "passive"))
      (node (ref "X37") (pin "1") (pinfunction "1_1") (pintype "passive"))
    )
    (net (code "51") (name "Net-(R479-Pad1)") (class "Default")
      (node (ref "R479") (pin "1") (pinfunction "1_1") (pintype "passive"))
      (node (ref "X34") (pin "1") (pinfunction "1_1") (pintype "passive"))
    )
    (net (code "52") (name "Net-(R481-Pad1)") (class "Default")
      (node (ref "R481") (pin "1") (pinfunction "1_1") (pintype "passive"))
      (node (ref "X34") (pin "3") (pinfunction "3_3") (pintype "passive"))
    )
    (net (code "53") (name "Net-(R482-Pad1)") (class "Default")
      (node (ref "R482") (pin "1") (pinfunction "1_1") (pintype "passive"))
      (node (ref "R484") (pin "1") (pinfunction "1_1") (pintype "passive"))
      (node (ref "X34") (pin "4") (pinfunction "4_4") (pintype "passive"))
    )
    (net (code "54") (name "Net-(R483-Pad1)") (class "Default")
      (node (ref "R483") (pin "1") (pinfunction "1_1") (pintype "passive"))
      (node (ref "R485") (pin "1") (pinfunction "1_1") (pintype "passive"))
      (node (ref "X34") (pin "5") (pinfunction "5_5") (pintype "passive"))
    )
    (net (code "55") (name "Net-(S1-A)") (class "Default")
      (node (ref "R411") (pin "2") (pinfunction "2_2") (pintype "passive"))
      (node (ref "S1") (pin "L1") (pinfunction "A_L1") (pintype "passive"))
    )
    (net (code "56") (name "Net-(V86-D)") (class "Default")
      (node (ref "R664") (pin "1") (pinfunction "1_1") (pintype "passive"))
      (node (ref "V86") (pin "3") (pinfunction "D_3") (pintype "passive"))
    )
    (net (code "57") (name "Net-(VD42-A)") (class "Default")
      (node (ref "VD42") (pin "2") (pinfunction "A_2") (pintype "passive"))
      (node (ref "VT9") (pin "D") (pinfunction "D_D") (pintype "passive"))
      (node (ref "X24") (pin "2") (pinfunction "2_2") (pintype "passive"))
    )
    (net (code "58") (name "Net-(VD42-K)") (class "Default")
      (node (ref "C17") (pin "1") (pinfunction "1_1") (pintype "passive"))
      (node (ref "C23") (pin "2") (pinfunction "2_2") (pintype "passive"))
      (node (ref "L17") (pin "2") (pinfunction "2_2") (pintype "passive"))
      (node (ref "VD42") (pin "1") (pinfunction "K_1") (pintype "passive"))
      (node (ref "X24") (pin "1") (pinfunction "1_1") (pintype "passive"))
    )
    (net (code "59") (name "Net-(VT84-D)") (class "Default")
      (node (ref "R662") (pin "1") (pinfunction "1_1") (pintype "passive"))
      (node (ref "VT84") (pin "3") (pinfunction "D_3") (pintype "passive"))
    )
    (net (code "60") (name "Net-(VT85-D)") (class "Default")
      (node (ref "R663") (pin "1") (pinfunction "1_1") (pintype "passive"))
      (node (ref "VT85") (pin "3") (pinfunction "D_3") (pintype "passive"))
    )
    (net (code "61") (name "Net-(X41A-CC1)") (class "Default")
      (node (ref "R110") (pin "1") (pinfunction "1_1") (pintype "passive"))
      (node (ref "X41") (pin "A5") (pinfunction "CC1_A5") (pintype "passive"))
    )
    (net (code "62") (name "Net-(X41A-CC2)") (class "Default")
      (node (ref "R111") (pin "1") (pinfunction "1_1") (pintype "passive"))
      (node (ref "X41") (pin "B5") (pinfunction "CC2_B5") (pintype "passive"))
    )
    (net (code "63") (name "SH") (class "Default")
      (node (ref "C416") (pin "2") (pinfunction "2_2") (pintype "passive"))
      (node (ref "R112") (pin "2") (pinfunction "2_2") (pintype "passive"))
    )
    (net (code "64") (name "VCC5V0_DEVICE_S0") (class "Default")
      (node (ref "VD43") (pin "2") (pinfunction "A_2") (pintype "passive"))
    )
    (net (code "65") (name "VCC5V0_SYS_S5") (class "Default")
      (node (ref "R418") (pin "2") (pinfunction "2_2") (pintype "passive"))
    )
    (net (code "66") (name "VCCA1V8_PLDO2_S0") (class "Default")
      (node (ref "R408") (pin "1") (pinfunction "1_1") (pintype "passive"))
      (node (ref "R409") (pin "1") (pinfunction "1_1") (pintype "passive"))
      (node (ref "R414") (pin "1") (pinfunction "1_1") (pintype "passive"))
      (node (ref "R415") (pin "1") (pinfunction "1_1") (pintype "passive"))
      (node (ref "R421") (pin "1") (pinfunction "1_1") (pintype "passive"))
    )
    (net (code "67") (name "VCC_3V3_S0") (class "Default")
      (node (ref "HL10") (pin "2") (pinfunction "2_2") (pintype "passive"))
    )
    (net (code "68") (name "VCC_3V3_S3") (class "Default")
      (node (ref "C588") (pin "1") (pinfunction "1_1") (pintype "passive"))
      (node (ref "C589") (pin "1") (pinfunction "1_1") (pintype "passive"))
      (node (ref "R411") (pin "1") (pinfunction "1_1") (pintype "passive"))
      (node (ref "R478") (pin "2") (pinfunction "2_2") (pintype "passive"))
      (node (ref "X34") (pin "2") (pinfunction "2_2") (pintype "passive"))
      (node (ref "X34") (pin "7") (pinfunction "7_7") (pintype "passive"))
      (node (ref "X37") (pin "3") (pinfunction "3_3") (pintype "passive"))
    )
    (net (code "69") (name "unconnected-(D26-TNOW-Pad6)") (class "Default")
      (node (ref "D26") (pin "6") (pinfunction "TNOW_6") (pintype "passive+no_connect"))
    )
    (net (code "70") (name "unconnected-(D26-~{CTS}-Pad5)") (class "Default")
      (node (ref "D26") (pin "5") (pinfunction "~{CTS}_5") (pintype "passive+no_connect"))
    )
    (net (code "71") (name "unconnected-(D26-~{RTS}-Pad4)") (class "Default")
      (node (ref "D26") (pin "4") (pinfunction "~{RTS}_4") (pintype "passive+no_connect"))
    )
    (net (code "72") (name "unconnected-(X36-Pad1)") (class "Default")
      (node (ref "X36") (pin "1") (pinfunction "1_1") (pintype "passive+no_connect"))
    )
    (net (code "73") (name "unconnected-(X36-Pad2)") (class "Default")
      (node (ref "X36") (pin "2") (pinfunction "2_2") (pintype "passive+no_connect"))
    )
    (net (code "74") (name "unconnected-(X41B-GND-PadH1)") (class "Default")
      (node (ref "X41") (pin "H1") (pinfunction "GND_H1") (pintype "passive+no_connect"))
    )
    (net (code "75") (name "unconnected-(X41B-GND-PadH2)") (class "Default")
      (node (ref "X41") (pin "H2") (pinfunction "GND_H2") (pintype "passive+no_connect"))
    )
    (net (code "76") (name "unconnected-(X41B-SBU1-PadA8)") (class "Default")
      (node (ref "X41") (pin "A8") (pinfunction "SBU1_A8") (pintype "passive+no_connect"))
    )
    (net (code "77") (name "unconnected-(X41B-SBU2-PadB8)") (class "Default")
      (node (ref "X41") (pin "B8") (pinfunction "SBU2_B8") (pintype "passive+no_connect"))
    )
    (net (code "78") (name "unconnected-(X41B-SSRX1_N-PadB10)") (class "Default")
      (node (ref "X41") (pin "B10") (pinfunction "SSRX1_N_B10") (pintype "passive+no_connect"))
    )
    (net (code "79") (name "unconnected-(X41B-SSRX1_P-PadB11)") (class "Default")
      (node (ref "X41") (pin "B11") (pinfunction "SSRX1_P_B11") (pintype "passive+no_connect"))
    )
    (net (code "80") (name "unconnected-(X41B-SSRX2_N-PadA10)") (class "Default")
      (node (ref "X41") (pin "A10") (pinfunction "SSRX2_N_A10") (pintype "passive+no_connect"))
    )
    (net (code "81") (name "unconnected-(X41B-SSRX2_P-PadA11)") (class "Default")
      (node (ref "X41") (pin "A11") (pinfunction "SSRX2_P_A11") (pintype "passive+no_connect"))
    )
    (net (code "82") (name "unconnected-(X41B-SSTX1_N-PadA3)") (class "Default")
      (node (ref "X41") (pin "A3") (pinfunction "SSTX1_N_A3") (pintype "passive+no_connect"))
    )
    (net (code "83") (name "unconnected-(X41B-SSTX1_P-PadA2)") (class "Default")
      (node (ref "X41") (pin "A2") (pinfunction "SSTX1_P_A2") (pintype "passive+no_connect"))
    )
    (net (code "84") (name "unconnected-(X41B-SSTX2_N-PadB3)") (class "Default")
      (node (ref "X41") (pin "B3") (pinfunction "SSTX2_N_B3") (pintype "passive+no_connect"))
    )
    (net (code "85") (name "unconnected-(X41B-SSTX2_P-PadB2)") (class "Default")
      (node (ref "X41") (pin "B2") (pinfunction "SSTX2_P_B2") (pintype "passive+no_connect"))
    )
  )
)
